# schematic_main.net
KiCad netlist of a schematic drawn in Altium Designer
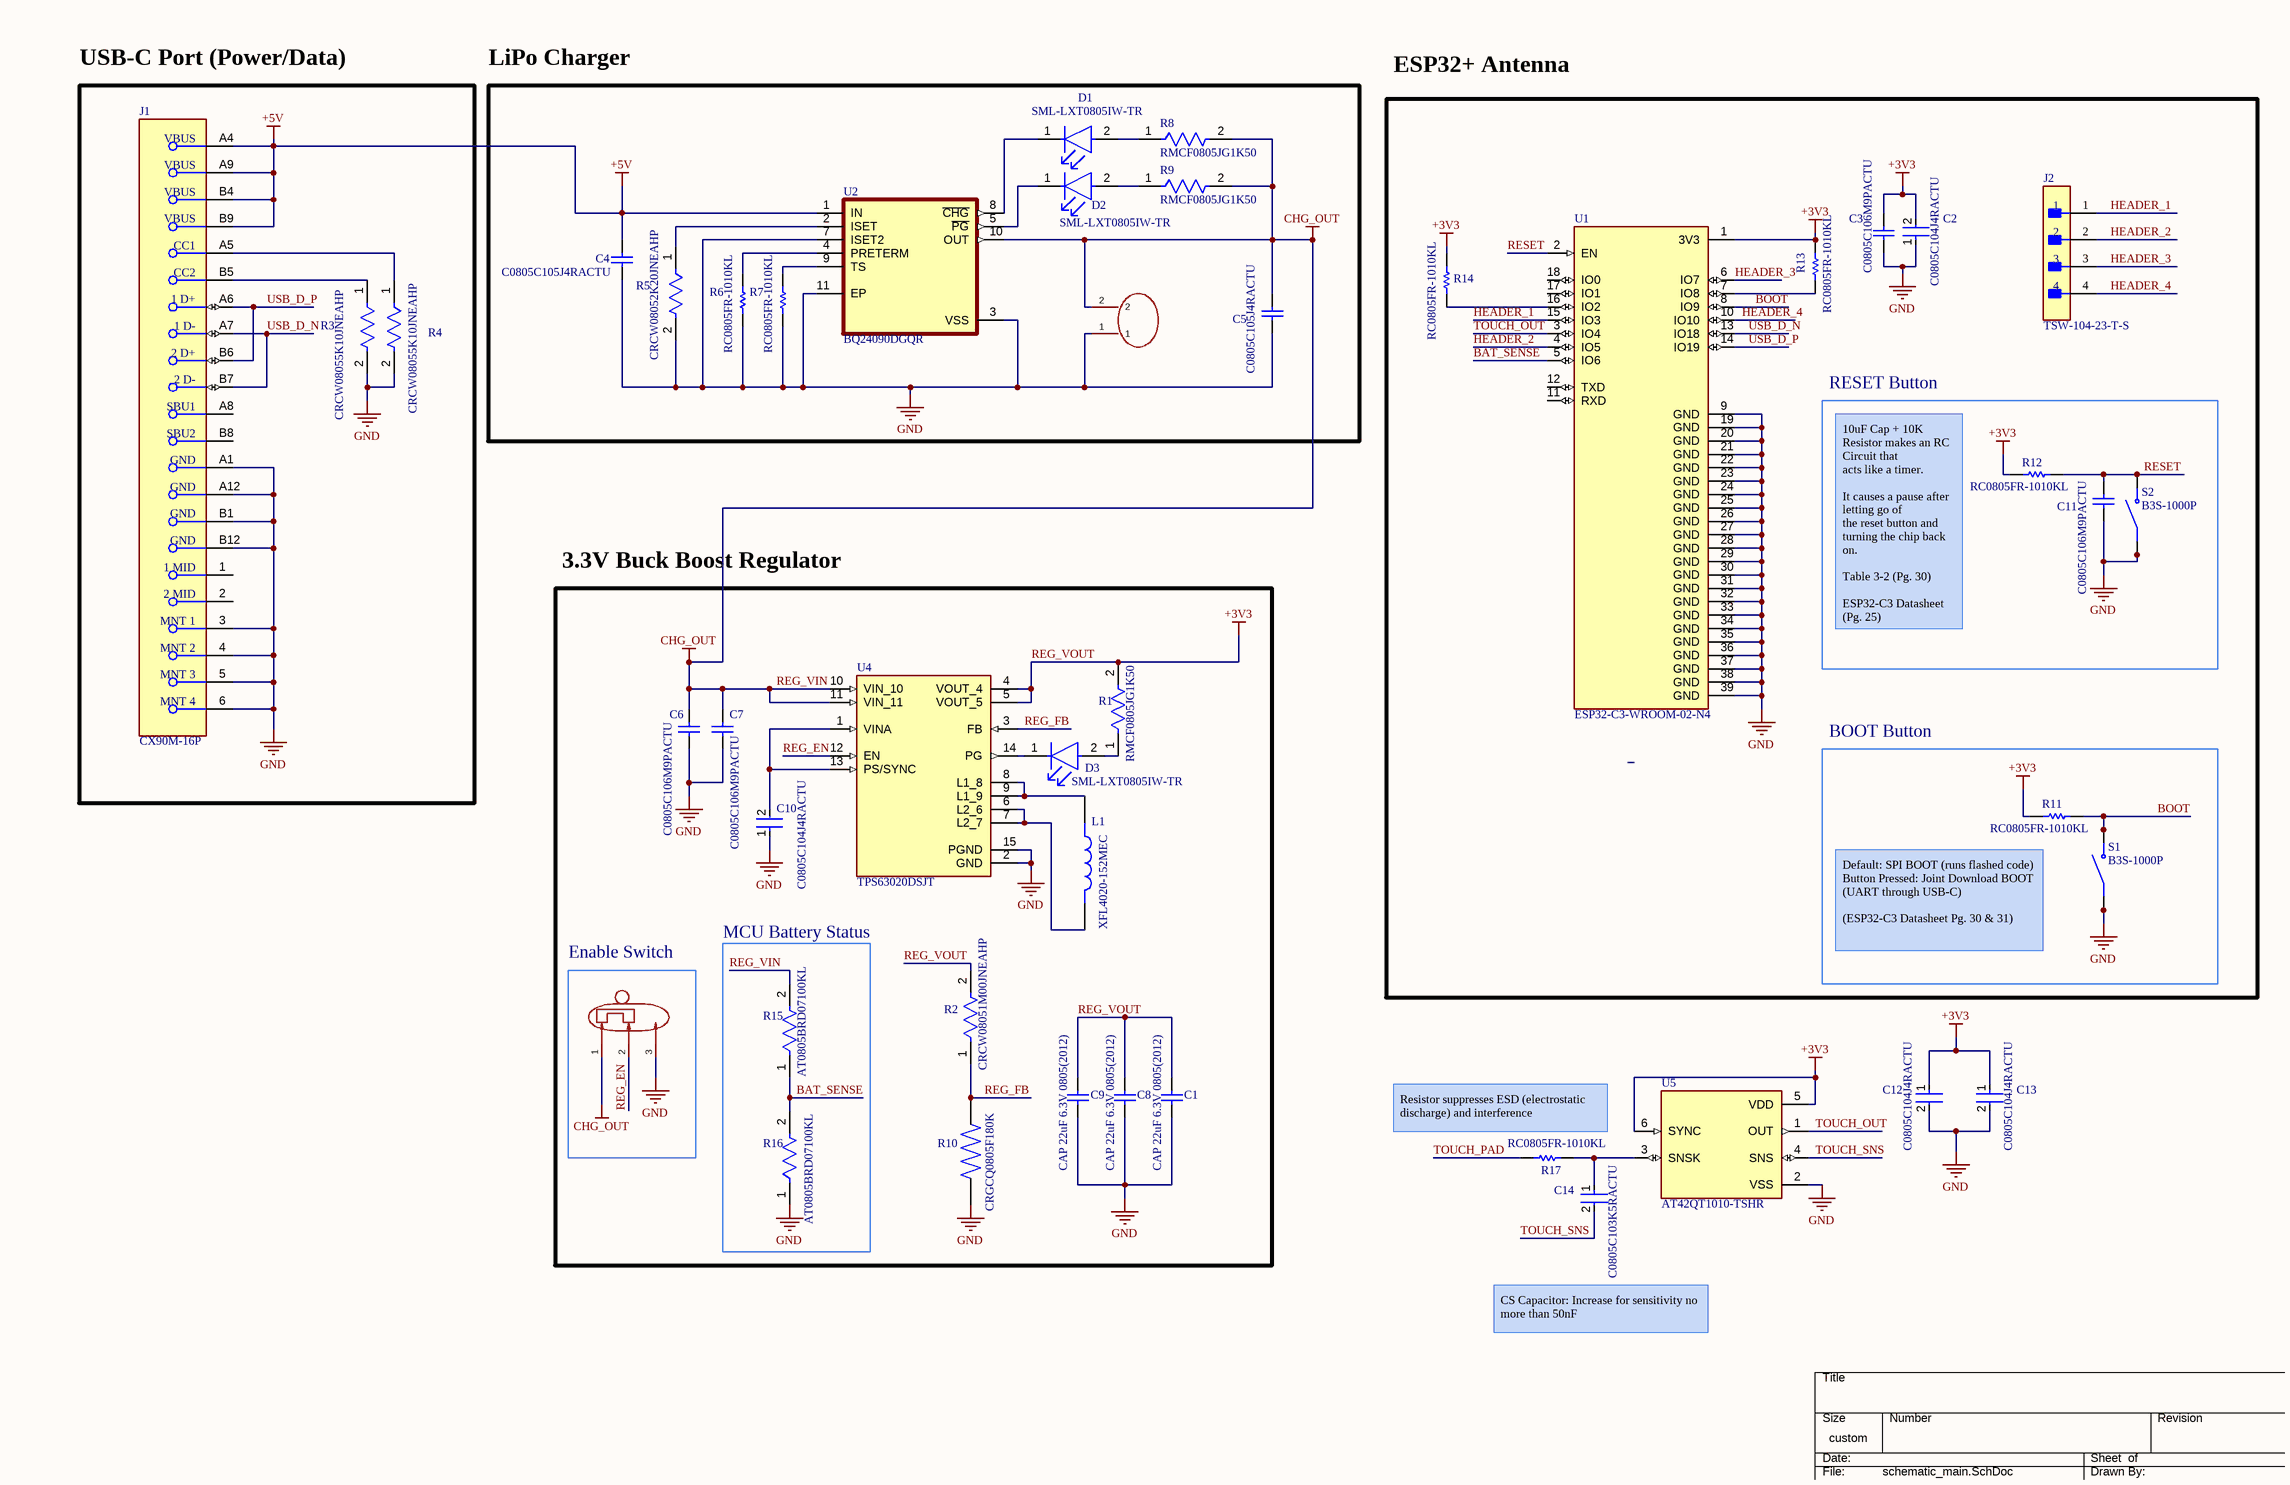
[diagram p0: schematic_main.SchDoc]

(export (version "E")
  (design (tool "Eeschema 10.0.6"))
  (components
    (comp (ref "C1")
      (value "CAP 22uF 6.3V 0805(2012)")
      (footprint "CAPC0805(2012)145_L")
      (description "CAP 22uF 6.3V ±10% 0805 (2012 Metric) Thickness 1.45mm SMD")
      (fields (field (name "TOLERANCE") "Â±10%"))
      (libsource (lib "schematic_library") (part "CMP-1036-04938-1"))
    )
    (comp (ref "C2")
      (value "C0805C104J4RACTU")
      (footprint "FP-C0805C-DN-IPC_A")
      (description "CAP CER 0.1UF 16V X7R 0805")
      (fields
        (field (name "OCTOPART") "https://octopart.com/c0805c104j4ractu-kemet-12563748")
        (field (name "MANUFACTURER") "KEMET")
      )
      (libsource (lib "schematic_library") (part "CMP-2007-01112-2"))
    )
    (comp (ref "C3")
      (value "C0805C106M9PACTU")
      (footprint "CAPC2013X145X50LL20T25")
      (description "CAP CER 10UF 6.3V X5R 0805")
      (fields (field (name "MANUFACTURER") "Kemet"))
      (libsource (lib "schematic_library") (part "CMP-1036-04919-2"))
    )
    (comp (ref "C4")
      (value "C0805C105J4RACTU")
      (footprint "CAPC2013X140X50LL20T25")
      (description "1 µF ±5% 16V Ceramic Capacitor X7R 0805 (2012 Metric)")
      (fields (field (name "MANUFACTURER") "Kemet"))
      (libsource (lib "schematic_library") (part "CMP-2007-03229-1"))
    )
    (comp (ref "C5")
      (value "C0805C105J4RACTU")
      (footprint "CAPC2013X140X50LL20T25")
      (description "1 µF ±5% 16V Ceramic Capacitor X7R 0805 (2012 Metric)")
      (fields (field (name "MANUFACTURER") "Kemet"))
      (libsource (lib "schematic_library") (part "CMP-2007-03229-1"))
    )
    (comp (ref "C6")
      (value "C0805C106M9PACTU")
      (footprint "CAPC2013X145X50LL20T25")
      (description "CAP CER 10UF 6.3V X5R 0805")
      (fields (field (name "MANUFACTURER") "Kemet"))
      (libsource (lib "schematic_library") (part "CMP-1036-04919-2"))
    )
    (comp (ref "C7")
      (value "C0805C106M9PACTU")
      (footprint "CAPC2013X145X50LL20T25")
      (description "CAP CER 10UF 6.3V X5R 0805")
      (fields (field (name "MANUFACTURER") "Kemet"))
      (libsource (lib "schematic_library") (part "CMP-1036-04919-2"))
    )
    (comp (ref "C8")
      (value "CAP 22uF 6.3V 0805(2012)")
      (footprint "CAPC0805(2012)145_L")
      (description "CAP 22uF 6.3V ±10% 0805 (2012 Metric) Thickness 1.45mm SMD")
      (fields (field (name "TOLERANCE") "Â±10%"))
      (libsource (lib "schematic_library") (part "CMP-1036-04938-1"))
    )
    (comp (ref "C9")
      (value "CAP 22uF 6.3V 0805(2012)")
      (footprint "CAPC0805(2012)145_L")
      (description "CAP 22uF 6.3V ±10% 0805 (2012 Metric) Thickness 1.45mm SMD")
      (fields (field (name "TOLERANCE") "Â±10%"))
      (libsource (lib "schematic_library") (part "CMP-1036-04938-1"))
    )
    (comp (ref "C10")
      (value "C0805C104J4RACTU")
      (footprint "FP-C0805C-DN-IPC_A")
      (description "CAP CER 0.1UF 16V X7R 0805")
      (fields
        (field (name "OCTOPART") "https://octopart.com/c0805c104j4ractu-kemet-12563748")
        (field (name "MANUFACTURER") "KEMET")
      )
      (libsource (lib "schematic_library") (part "CMP-2007-01112-2"))
    )
    (comp (ref "C11")
      (value "C0805C106M9PACTU")
      (footprint "CAPC2013X145X50LL20T25")
      (description "CAP CER 10UF 6.3V X5R 0805")
      (fields (field (name "MANUFACTURER") "Kemet"))
      (libsource (lib "schematic_library") (part "CMP-1036-04919-2"))
    )
    (comp (ref "C12")
      (value "C0805C104J4RACTU")
      (footprint "FP-C0805C-DN-IPC_A")
      (description "CAP CER 0.1UF 16V X7R 0805")
      (fields
        (field (name "OCTOPART") "https://octopart.com/c0805c104j4ractu-kemet-12563748")
        (field (name "MANUFACTURER") "KEMET")
      )
      (libsource (lib "schematic_library") (part "CMP-2007-01112-2"))
    )
    (comp (ref "C13")
      (value "C0805C104J4RACTU")
      (footprint "FP-C0805C-DN-IPC_A")
      (description "CAP CER 0.1UF 16V X7R 0805")
      (fields
        (field (name "OCTOPART") "https://octopart.com/c0805c104j4ractu-kemet-12563748")
        (field (name "MANUFACTURER") "KEMET")
      )
      (libsource (lib "schematic_library") (part "CMP-2007-01112-2"))
    )
    (comp (ref "C14")
      (value "C0805C103K5RACTU")
      (footprint "FP-C0805C-DN-IPC_A")
      (description "CAP CER 10000PF 50V X7R 0805")
      (fields
        (field (name "TOLERANCE") "0.1")
        (field (name "OCTOPART") "https://octopart.com/c0805c103k5ractu-kemet-90536")
      )
      (libsource (lib "schematic_library") (part "CMP-2007-01079-2"))
    )
    (comp (ref "CN1")
      (value "b2b-ph-k-s(lf)(sn)")
      (footprint "CONN-TH_B2B-PH-K-S")
      (fields (field (name "MANUFACTURER") "JST") (field (name "MANUFACTURERPART") "B2B-PH-K-S(LF)(SN)"))
      (libsource (lib "schematic_library") (part "b2b-ph-k-s(lf)(sn)"))
    )
    (comp (ref "D1")
      (value "SML-LXT0805IW-TR")
      (footprint "FP-SML-LXT0805IW-TR-MFG")
      (description "LED RED DIFFUSED SMD")
      (libsource (lib "schematic_library") (part "CMP-1724-00002-2"))
    )
    (comp (ref "D2")
      (value "SML-LXT0805IW-TR")
      (footprint "FP-SML-LXT0805IW-TR-MFG")
      (description "LED RED DIFFUSED SMD")
      (libsource (lib "schematic_library") (part "CMP-1724-00002-2"))
    )
    (comp (ref "D3")
      (value "SML-LXT0805IW-TR")
      (footprint "FP-SML-LXT0805IW-TR-MFG")
      (description "LED RED DIFFUSED SMD")
      (libsource (lib "schematic_library") (part "CMP-1724-00002-2"))
    )
    (comp (ref "J1")
      (value "CX90M-16P")
      (footprint "FP-CX90M-16P-MFG")
      (description "CONN RCPT USB2.0 TYPEC 16POS SMD")
      (libsource (lib "schematic_library") (part "CMP-11601-000005-1"))
    )
    (comp (ref "J2")
      (value "TSW-104-23-T-S")
      (footprint "FP-TSW-104-23-T-S-MFG")
      (description "CONN HEADER VERT 4POS 2.54MM")
      (libsource (lib "schematic_library") (part "CMP-02766-001388-1"))
    )
    (comp (ref "L1")
      (value "XFL4020-152MEC")
      (footprint "IND_XFL4020-152MEC")
      (fields (field (name "MF") "Coilcraft"))
      (libsource (lib "schematic_library") (part "XFL4020-152MEC"))
    )
    (comp (ref "R1")
      (value "RMCF0805JG1K50")
      (footprint "FP-RMCF0805-IPC_A")
      (description "1.5kΩ ±5% 0.125W 0805 Thick Film Chip Resistor AEC-Q200 compliant")
      (fields (field (name "TOLERANCE") "5%"))
      (libsource (lib "schematic_library") (part "CMP-26527-004339-1"))
    )
    (comp (ref "R2")
      (value "CRCW08051M00JNEAHP")
      (footprint "FP-CRCW0805-HPe3-IPC_A")
      (description "RES Thick Film, 1MΩ, 5%, 0.5W, 200ppm/°C, 0805")
      (fields (field (name "TOLERANCE") "5%"))
      (libsource (lib "schematic_library") (part "CMP-02407-004826-1"))
    )
    (comp (ref "R3")
      (value "CRCW08055K10JNEAHP")
      (footprint "FP-CRCW0805-HPe3-IPC_A")
      (description "RES Thick Film, 5.1kΩ, 5%, 0.5W, 200ppm/°C, 0805")
      (fields (field (name "TOLERANCE") "5%"))
      (libsource (lib "schematic_library") (part "CMP-02407-002962-1"))
    )
    (comp (ref "R4")
      (value "CRCW08055K10JNEAHP")
      (footprint "FP-CRCW0805-HPe3-IPC_A")
      (description "RES Thick Film, 5.1kΩ, 5%, 0.5W, 200ppm/°C, 0805")
      (fields (field (name "TOLERANCE") "5%"))
      (libsource (lib "schematic_library") (part "CMP-02407-002962-1"))
    )
    (comp (ref "R5")
      (value "CRCW08052K20JNEAHP")
      (footprint "FP-CRCW0805-HPe3-IPC_A")
      (description "RES Thick Film, 2.2kΩ, 5%, 0.5W, 200ppm/°C, 0805")
      (fields (field (name "TOLERANCE") "5%"))
      (libsource (lib "schematic_library") (part "CMP-02407-006246-1"))
    )
    (comp (ref "R6")
      (value "RC0805FR-1010KL")
      (footprint "RESC2013X60X35LL10T20")
      (description "RES 10K OHM 1% 1/8W 0805")
      (fields (field (name "MANUFACTURER") "Yageo"))
      (libsource (lib "schematic_library") (part "CMP-2001-04512-1"))
    )
    (comp (ref "R7")
      (value "RC0805FR-1010KL")
      (footprint "RESC2013X60X35LL10T20")
      (description "RES 10K OHM 1% 1/8W 0805")
      (fields (field (name "MANUFACTURER") "Yageo"))
      (libsource (lib "schematic_library") (part "CMP-2001-04512-1"))
    )
    (comp (ref "R8")
      (value "RMCF0805JG1K50")
      (footprint "FP-RMCF0805-IPC_A")
      (description "1.5kΩ ±5% 0.125W 0805 Thick Film Chip Resistor AEC-Q200 compliant")
      (fields (field (name "TOLERANCE") "5%"))
      (libsource (lib "schematic_library") (part "CMP-26527-004339-1"))
    )
    (comp (ref "R9")
      (value "RMCF0805JG1K50")
      (footprint "FP-RMCF0805-IPC_A")
      (description "1.5kΩ ±5% 0.125W 0805 Thick Film Chip Resistor AEC-Q200 compliant")
      (fields (field (name "TOLERANCE") "5%"))
      (libsource (lib "schematic_library") (part "CMP-26527-004339-1"))
    )
    (comp (ref "R10")
      (value "CRGCQ0805F180K")
      (footprint "RESC2012X65N")
      (fields (field (name "MF") "TE Connectivity"))
      (libsource (lib "schematic_library") (part "CRGCQ0805F180K"))
    )
    (comp (ref "R11")
      (value "RC0805FR-1010KL")
      (footprint "RESC2013X60X35LL10T20")
      (description "RES 10K OHM 1% 1/8W 0805")
      (fields (field (name "MANUFACTURER") "Yageo"))
      (libsource (lib "schematic_library") (part "CMP-2001-04512-1"))
    )
    (comp (ref "R12")
      (value "RC0805FR-1010KL")
      (footprint "RESC2013X60X35LL10T20")
      (description "RES 10K OHM 1% 1/8W 0805")
      (fields (field (name "MANUFACTURER") "Yageo"))
      (libsource (lib "schematic_library") (part "CMP-2001-04512-1"))
    )
    (comp (ref "R13")
      (value "RC0805FR-1010KL")
      (footprint "RESC2013X60X35LL10T20")
      (description "RES 10K OHM 1% 1/8W 0805")
      (fields (field (name "MANUFACTURER") "Yageo"))
      (libsource (lib "schematic_library") (part "CMP-2001-04512-1"))
    )
    (comp (ref "R14")
      (value "RC0805FR-1010KL")
      (footprint "RESC2013X60X35LL10T20")
      (description "RES 10K OHM 1% 1/8W 0805")
      (fields (field (name "MANUFACTURER") "Yageo"))
      (libsource (lib "schematic_library") (part "CMP-2001-04512-1"))
    )
    (comp (ref "R15")
      (value "AT0805BRD07100KL")
      (footprint "FP-AT0805-IPC_A")
      (description "Thin Film Chip Resistors Automotive Grade 100kΩ 0.1% 25ppm/°C 0805")
      (fields (field (name "TOLERANCE") "0.1%"))
      (libsource (lib "schematic_library") (part "CMP-03412-042085-1"))
    )
    (comp (ref "R16")
      (value "AT0805BRD07100KL")
      (footprint "FP-AT0805-IPC_A")
      (description "Thin Film Chip Resistors Automotive Grade 100kΩ 0.1% 25ppm/°C 0805")
      (fields (field (name "TOLERANCE") "0.1%"))
      (libsource (lib "schematic_library") (part "CMP-03412-042085-1"))
    )
    (comp (ref "R17")
      (value "RC0805FR-1010KL")
      (footprint "RESC2013X60X35LL10T20")
      (description "RES 10K OHM 1% 1/8W 0805")
      (fields (field (name "MANUFACTURER") "Yageo"))
      (libsource (lib "schematic_library") (part "CMP-2001-04512-1"))
    )
    (comp (ref "S1")
      (value "B3S-1000P")
      (footprint "SW_B3S-1000P")
      (description "Tactile Switch SPST-NO Top Actuated Surface Mount")
      (libsource (lib "schematic_library") (part "B3S-1000P"))
    )
    (comp (ref "S2")
      (value "B3S-1000P")
      (footprint "SW_B3S-1000P")
      (description "Tactile Switch SPST-NO Top Actuated Surface Mount")
      (libsource (lib "schematic_library") (part "B3S-1000P"))
    )
    (comp (ref "U1")
      (value "ESP32-C3-WROOM-02-N4")
      (footprint "MODULE_ESP32-C3-WROOM-02-H4")
      (fields (field (name "MF") "Espressif Systems"))
      (libsource (lib "schematic_library") (part "ESP32-C3-WROOM-02-N4"))
    )
    (comp (ref "U2")
      (value "BQ24090DGQR")
      (footprint "IC_XTR111AIDGQR")
      (description "1-cell, 1-A, Li-ion linear battery charger w/ 10kÎ© NTC")
      (fields (field (name "MF") "Texas Instruments"))
      (libsource (lib "schematic_library") (part "BQ24090DGQR"))
    )
    (comp (ref "U3")
      (value "ss-12d00-g3")
      (footprint "SW-TH_3P-L8.8-W3.9-P2.50_SS12D00G3")
      (fields (field (name "MANUFACTURER") "SOFNG(硕方)") (field (name "MANUFACTURERPART") "SS-12D00-G3"))
      (libsource (lib "schematic_library") (part "ss-12d00-g3"))
    )
    (comp (ref "U4")
      (value "TPS63020DSJT")
      (footprint "IC_TPS63020DSJT")
      (description "High Efficiency Single Inductor Buck-Boost Converter with 4A Switch")
      (fields (field (name "MF") "Texas Instruments"))
      (libsource (lib "schematic_library") (part "TPS63020DSJT"))
    )
    (comp (ref "U5")
      (value "AT42QT1010-TSHR")
      (footprint "SOT95P270X145-6N")
      (description "Capacitive Touch Buttons SOT-23-6")
      (fields (field (name "MF") "Microchip"))
      (libsource (lib "schematic_library") (part "AT42QT1010-TSHR"))
    )
  )
  (nets
    (net (code "1") (name "+3V3") (class "Default")
      (node (ref "C1") (pin "1") (pinfunction "1_1") (pintype "passive"))
      (node (ref "C12") (pin "1") (pinfunction "1_1") (pintype "passive"))
      (node (ref "C13") (pin "1") (pinfunction "1_1") (pintype "passive"))
      (node (ref "C2") (pin "2") (pinfunction "2_2") (pintype "passive"))
      (node (ref "C3") (pin "1") (pinfunction "1_1") (pintype "passive"))
      (node (ref "C8") (pin "1") (pinfunction "1_1") (pintype "passive"))
      (node (ref "C9") (pin "1") (pinfunction "1_1") (pintype "passive"))
      (node (ref "R1") (pin "2") (pinfunction "2_2") (pintype "passive"))
      (node (ref "R11") (pin "1") (pinfunction "1_1") (pintype "passive"))
      (node (ref "R12") (pin "1") (pinfunction "1_1") (pintype "passive"))
      (node (ref "R13") (pin "2") (pinfunction "2_2") (pintype "passive"))
      (node (ref "R14") (pin "2") (pinfunction "2_2") (pintype "passive"))
      (node (ref "R2") (pin "2") (pinfunction "2_2") (pintype "passive"))
      (node (ref "U1") (pin "1") (pinfunction "3V3_1") (pintype "power_in"))
      (node (ref "U4") (pin "4") (pinfunction "VOUT_4_4") (pintype "power_in"))
      (node (ref "U4") (pin "5") (pinfunction "VOUT_5_5") (pintype "power_in"))
      (node (ref "U5") (pin "5") (pinfunction "VDD_5") (pintype "power_in"))
      (node (ref "U5") (pin "6") (pinfunction "SYNC_6") (pintype "input"))
    )
    (net (code "2") (name "+5V") (class "Default")
      (node (ref "C4") (pin "2") (pinfunction "2_2") (pintype "passive"))
      (node (ref "J1") (pin "A4") (pinfunction "VBUS_A4") (pintype "power_in"))
      (node (ref "J1") (pin "A9") (pinfunction "VBUS_A9") (pintype "power_in"))
      (node (ref "J1") (pin "B4") (pinfunction "VBUS_B4") (pintype "power_in"))
      (node (ref "J1") (pin "B9") (pinfunction "VBUS_B9") (pintype "power_in"))
      (node (ref "U2") (pin "1") (pinfunction "IN_1") (pintype "passive"))
    )
    (net (code "3") (name "/BAT_SENSE") (class "Default")
      (node (ref "R15") (pin "1") (pinfunction "1_1") (pintype "passive"))
      (node (ref "R16") (pin "2") (pinfunction "2_2") (pintype "passive"))
      (node (ref "U1") (pin "5") (pinfunction "IO6_5") (pintype "bidirectional"))
    )
    (net (code "4") (name "/BOOT") (class "Default")
      (node (ref "R11") (pin "2") (pinfunction "2_2") (pintype "passive"))
      (node (ref "S1") (pin "3") (pinfunction "NO_3") (pintype "passive"))
      (node (ref "S1") (pin "4") (pinfunction "NO_4") (pintype "passive"))
      (node (ref "U1") (pin "8") (pinfunction "IO9_8") (pintype "bidirectional"))
    )
    (net (code "5") (name "/HEADER_1") (class "Default")
      (node (ref "J2") (pin "1") (pinfunction "1_1") (pintype "passive"))
      (node (ref "U1") (pin "15") (pinfunction "IO3_15") (pintype "bidirectional"))
    )
    (net (code "6") (name "/HEADER_2") (class "Default")
      (node (ref "J2") (pin "2") (pinfunction "2_2") (pintype "passive"))
      (node (ref "U1") (pin "4") (pinfunction "IO5_4") (pintype "bidirectional"))
    )
    (net (code "7") (name "/HEADER_3") (class "Default")
      (node (ref "J2") (pin "3") (pinfunction "3_3") (pintype "passive"))
      (node (ref "U1") (pin "6") (pinfunction "IO7_6") (pintype "bidirectional"))
    )
    (net (code "8") (name "/HEADER_4") (class "Default")
      (node (ref "J2") (pin "4") (pinfunction "4_4") (pintype "passive"))
      (node (ref "U1") (pin "10") (pinfunction "IO10_10") (pintype "bidirectional"))
    )
    (net (code "9") (name "/REG_EN") (class "Default")
      (node (ref "U3") (pin "2") (pinfunction "2_2") (pintype "passive"))
      (node (ref "U4") (pin "12") (pinfunction "EN_12") (pintype "input"))
    )
    (net (code "10") (name "/REG_FB") (class "Default")
      (node (ref "R10") (pin "2") (pinfunction "2_2") (pintype "passive"))
      (node (ref "R2") (pin "1") (pinfunction "1_1") (pintype "passive"))
      (node (ref "U4") (pin "3") (pinfunction "FB_3") (pintype "input"))
    )
    (net (code "11") (name "/RESET") (class "Default")
      (node (ref "C11") (pin "2") (pinfunction "2_2") (pintype "passive"))
      (node (ref "R12") (pin "2") (pinfunction "2_2") (pintype "passive"))
      (node (ref "S2") (pin "3") (pinfunction "NO_3") (pintype "passive"))
      (node (ref "S2") (pin "4") (pinfunction "NO_4") (pintype "passive"))
      (node (ref "U1") (pin "2") (pinfunction "EN_2") (pintype "input"))
    )
    (net (code "12") (name "/TOUCH_OUT") (class "Default")
      (node (ref "U1") (pin "3") (pinfunction "IO4_3") (pintype "bidirectional"))
      (node (ref "U5") (pin "1") (pinfunction "OUT_1") (pintype "output"))
    )
    (net (code "13") (name "/TOUCH_PAD") (class "Default")
      (node (ref "R17") (pin "1") (pinfunction "1_1") (pintype "passive"))
    )
    (net (code "14") (name "/TOUCH_SNS") (class "Default")
      (node (ref "C14") (pin "2") (pinfunction "2_2") (pintype "passive"))
      (node (ref "U5") (pin "4") (pinfunction "SNS_4") (pintype "bidirectional"))
    )
    (net (code "15") (name "/USB_D_N") (class "Default")
      (node (ref "J1") (pin "A7") (pinfunction "1_D-_A7") (pintype "bidirectional"))
      (node (ref "J1") (pin "B7") (pinfunction "2_D-_B7") (pintype "bidirectional"))
      (node (ref "U1") (pin "13") (pinfunction "IO18_13") (pintype "bidirectional"))
    )
    (net (code "16") (name "/USB_D_P") (class "Default")
      (node (ref "J1") (pin "A6") (pinfunction "1_D+_A6") (pintype "bidirectional"))
      (node (ref "J1") (pin "B6") (pinfunction "2_D+_B6") (pintype "bidirectional"))
      (node (ref "U1") (pin "14") (pinfunction "IO19_14") (pintype "bidirectional"))
    )
    (net (code "17") (name "CHG_OUT") (class "Default")
      (node (ref "C5") (pin "2") (pinfunction "2_2") (pintype "passive"))
      (node (ref "C6") (pin "2") (pinfunction "2_2") (pintype "passive"))
      (node (ref "C7") (pin "2") (pinfunction "2_2") (pintype "passive"))
      (node (ref "CN1") (pin "2") (pinfunction "2_2") (pintype "passive"))
      (node (ref "R15") (pin "2") (pinfunction "2_2") (pintype "passive"))
      (node (ref "R8") (pin "2") (pinfunction "2_2") (pintype "passive"))
      (node (ref "R9") (pin "2") (pinfunction "2_2") (pintype "passive"))
      (node (ref "U2") (pin "10") (pinfunction "OUT_10") (pintype "output"))
      (node (ref "U3") (pin "1") (pinfunction "1_1") (pintype "passive"))
      (node (ref "U4") (pin "10") (pinfunction "VIN_10_10") (pintype "input"))
      (node (ref "U4") (pin "11") (pinfunction "VIN_11_11") (pintype "input"))
    )
    (net (code "18") (name "GND") (class "Default")
      (node (ref "C1") (pin "2") (pinfunction "2_2") (pintype "passive"))
      (node (ref "C10") (pin "1") (pinfunction "1_1") (pintype "passive"))
      (node (ref "C11") (pin "1") (pinfunction "1_1") (pintype "passive"))
      (node (ref "C12") (pin "2") (pinfunction "2_2") (pintype "passive"))
      (node (ref "C13") (pin "2") (pinfunction "2_2") (pintype "passive"))
      (node (ref "C2") (pin "1") (pinfunction "1_1") (pintype "passive"))
      (node (ref "C3") (pin "2") (pinfunction "2_2") (pintype "passive"))
      (node (ref "C4") (pin "1") (pinfunction "1_1") (pintype "passive"))
      (node (ref "C5") (pin "1") (pinfunction "1_1") (pintype "passive"))
      (node (ref "C6") (pin "1") (pinfunction "1_1") (pintype "passive"))
      (node (ref "C7") (pin "1") (pinfunction "1_1") (pintype "passive"))
      (node (ref "C8") (pin "2") (pinfunction "2_2") (pintype "passive"))
      (node (ref "C9") (pin "2") (pinfunction "2_2") (pintype "passive"))
      (node (ref "CN1") (pin "1") (pinfunction "1_1") (pintype "passive"))
      (node (ref "J1") (pin "3") (pinfunction "MNT_1_3") (pintype "passive"))
      (node (ref "J1") (pin "4") (pinfunction "MNT_2_4") (pintype "passive"))
      (node (ref "J1") (pin "5") (pinfunction "MNT_3_5") (pintype "passive"))
      (node (ref "J1") (pin "6") (pinfunction "MNT_4_6") (pintype "passive"))
      (node (ref "J1") (pin "A1") (pinfunction "GND_A1") (pintype "power_in"))
      (node (ref "J1") (pin "A12") (pinfunction "GND_A12") (pintype "power_in"))
      (node (ref "J1") (pin "B1") (pinfunction "GND_B1") (pintype "power_in"))
      (node (ref "J1") (pin "B12") (pinfunction "GND_B12") (pintype "power_in"))
      (node (ref "R10") (pin "1") (pinfunction "1_1") (pintype "passive"))
      (node (ref "R16") (pin "1") (pinfunction "1_1") (pintype "passive"))
      (node (ref "R3") (pin "2") (pinfunction "2_2") (pintype "passive"))
      (node (ref "R4") (pin "2") (pinfunction "2_2") (pintype "passive"))
      (node (ref "R5") (pin "2") (pinfunction "2_2") (pintype "passive"))
      (node (ref "R6") (pin "1") (pinfunction "1_1") (pintype "passive"))
      (node (ref "R7") (pin "1") (pinfunction "1_1") (pintype "passive"))
      (node (ref "S1") (pin "1") (pinfunction "COM_1") (pintype "passive"))
      (node (ref "S1") (pin "2") (pinfunction "COM_2") (pintype "passive"))
      (node (ref "S2") (pin "1") (pinfunction "COM_1") (pintype "passive"))
      (node (ref "S2") (pin "2") (pinfunction "COM_2") (pintype "passive"))
      (node (ref "U1") (pin "19") (pinfunction "GND_19") (pintype "power_in"))
      (node (ref "U1") (pin "20") (pinfunction "GND_20") (pintype "power_in"))
      (node (ref "U1") (pin "21") (pinfunction "GND_21") (pintype "power_in"))
      (node (ref "U1") (pin "22") (pinfunction "GND_22") (pintype "power_in"))
      (node (ref "U1") (pin "23") (pinfunction "GND_23") (pintype "power_in"))
      (node (ref "U1") (pin "24") (pinfunction "GND_24") (pintype "power_in"))
      (node (ref "U1") (pin "25") (pinfunction "GND_25") (pintype "power_in"))
      (node (ref "U1") (pin "26") (pinfunction "GND_26") (pintype "power_in"))
      (node (ref "U1") (pin "27") (pinfunction "GND_27") (pintype "power_in"))
      (node (ref "U1") (pin "28") (pinfunction "GND_28") (pintype "power_in"))
      (node (ref "U1") (pin "29") (pinfunction "GND_29") (pintype "power_in"))
      (node (ref "U1") (pin "30") (pinfunction "GND_30") (pintype "power_in"))
      (node (ref "U1") (pin "31") (pinfunction "GND_31") (pintype "power_in"))
      (node (ref "U1") (pin "32") (pinfunction "GND_32") (pintype "power_in"))
      (node (ref "U1") (pin "33") (pinfunction "GND_33") (pintype "power_in"))
      (node (ref "U1") (pin "34") (pinfunction "GND_34") (pintype "power_in"))
      (node (ref "U1") (pin "35") (pinfunction "GND_35") (pintype "power_in"))
      (node (ref "U1") (pin "36") (pinfunction "GND_36") (pintype "power_in"))
      (node (ref "U1") (pin "37") (pinfunction "GND_37") (pintype "power_in"))
      (node (ref "U1") (pin "38") (pinfunction "GND_38") (pintype "power_in"))
      (node (ref "U1") (pin "39") (pinfunction "GND_39") (pintype "power_in"))
      (node (ref "U1") (pin "9") (pinfunction "GND_9") (pintype "power_in"))
      (node (ref "U2") (pin "11") (pinfunction "EP_11") (pintype "power_in"))
      (node (ref "U2") (pin "3") (pinfunction "VSS_3") (pintype "power_in"))
      (node (ref "U2") (pin "7") (pinfunction "ISET2_7") (pintype "passive"))
      (node (ref "U3") (pin "3") (pinfunction "3_3") (pintype "passive"))
      (node (ref "U4") (pin "15") (pinfunction "PGND_15") (pintype "power_in"))
      (node (ref "U4") (pin "2") (pinfunction "GND_2") (pintype "power_in"))
      (node (ref "U5") (pin "2") (pinfunction "VSS_2") (pintype "power_in"))
    )
    (net (code "19") (name "Net-(D1-A)") (class "Default")
      (node (ref "D1") (pin "2") (pinfunction "A_2") (pintype "passive"))
      (node (ref "R8") (pin "1") (pinfunction "1_1") (pintype "passive"))
    )
    (net (code "20") (name "Net-(D1-C)") (class "Default")
      (node (ref "D1") (pin "1") (pinfunction "C_1") (pintype "passive"))
      (node (ref "U2") (pin "8") (pinfunction "~{CHG}_8") (pintype "output"))
    )
    (net (code "21") (name "Net-(D2-A)") (class "Default")
      (node (ref "D2") (pin "2") (pinfunction "A_2") (pintype "passive"))
      (node (ref "R9") (pin "1") (pinfunction "1_1") (pintype "passive"))
    )
    (net (code "22") (name "Net-(D2-C)") (class "Default")
      (node (ref "D2") (pin "1") (pinfunction "C_1") (pintype "passive"))
      (node (ref "U2") (pin "5") (pinfunction "~{PG}_5") (pintype "output"))
    )
    (net (code "23") (name "Net-(D3-A)") (class "Default")
      (node (ref "D3") (pin "2") (pinfunction "A_2") (pintype "passive"))
      (node (ref "R1") (pin "1") (pinfunction "1_1") (pintype "passive"))
    )
    (net (code "24") (name "Net-(D3-C)") (class "Default")
      (node (ref "D3") (pin "1") (pinfunction "C_1") (pintype "passive"))
      (node (ref "U4") (pin "14") (pinfunction "PG_14") (pintype "output"))
    )
    (net (code "25") (name "Net-(J1-CC1)") (class "Default")
      (node (ref "J1") (pin "A5") (pinfunction "CC1_A5") (pintype "passive"))
      (node (ref "R4") (pin "1") (pinfunction "1_1") (pintype "passive"))
    )
    (net (code "26") (name "Net-(J1-CC2)") (class "Default")
      (node (ref "J1") (pin "B5") (pinfunction "CC2_B5") (pintype "passive"))
      (node (ref "R3") (pin "1") (pinfunction "1_1") (pintype "passive"))
    )
    (net (code "27") (name "Net-(U1-IO2)") (class "Default")
      (node (ref "R14") (pin "1") (pinfunction "1_1") (pintype "passive"))
      (node (ref "U1") (pin "16") (pinfunction "IO2_16") (pintype "bidirectional"))
    )
    (net (code "28") (name "Net-(U1-IO8)") (class "Default")
      (node (ref "R13") (pin "1") (pinfunction "1_1") (pintype "passive"))
      (node (ref "U1") (pin "7") (pinfunction "IO8_7") (pintype "bidirectional"))
    )
    (net (code "29") (name "Net-(U2-ISET)") (class "Default")
      (node (ref "R5") (pin "1") (pinfunction "1_1") (pintype "passive"))
      (node (ref "U2") (pin "2") (pinfunction "ISET_2") (pintype "passive"))
    )
    (net (code "30") (name "Net-(U2-PRETERM)") (class "Default")
      (node (ref "R6") (pin "2") (pinfunction "2_2") (pintype "passive"))
      (node (ref "U2") (pin "4") (pinfunction "PRETERM_4") (pintype "passive"))
    )
    (net (code "31") (name "Net-(U2-TS)") (class "Default")
      (node (ref "R7") (pin "2") (pinfunction "2_2") (pintype "passive"))
      (node (ref "U2") (pin "9") (pinfunction "TS_9") (pintype "passive"))
    )
    (net (code "32") (name "Net-(U4-L1_8)") (class "Default")
      (node (ref "L1") (pin "1") (pinfunction "1_1") (pintype "passive"))
      (node (ref "U4") (pin "8") (pinfunction "L1_8_8") (pintype "passive"))
      (node (ref "U4") (pin "9") (pinfunction "L1_9_9") (pintype "passive"))
    )
    (net (code "33") (name "Net-(U4-L2_6)") (class "Default")
      (node (ref "L1") (pin "2") (pinfunction "2_2") (pintype "passive"))
      (node (ref "U4") (pin "6") (pinfunction "L2_6_6") (pintype "passive"))
      (node (ref "U4") (pin "7") (pinfunction "L2_7_7") (pintype "passive"))
    )
    (net (code "34") (name "Net-(U4-PS{slash}SYNC)") (class "Default")
      (node (ref "C10") (pin "2") (pinfunction "2_2") (pintype "passive"))
      (node (ref "U4") (pin "1") (pinfunction "VINA_1") (pintype "input"))
      (node (ref "U4") (pin "13") (pinfunction "PS/SYNC_13") (pintype "input"))
    )
    (net (code "35") (name "Net-(U5-SNSK)") (class "Default")
      (node (ref "C14") (pin "1") (pinfunction "1_1") (pintype "passive"))
      (node (ref "R17") (pin "2") (pinfunction "2_2") (pintype "passive"))
      (node (ref "U5") (pin "3") (pinfunction "SNSK_3") (pintype "bidirectional"))
    )
    (net (code "36") (name "unconnected-(J1-1_MID-Pad1)") (class "Default")
      (node (ref "J1") (pin "1") (pinfunction "1_MID_1") (pintype "passive"))
    )
    (net (code "37") (name "unconnected-(J1-2_MID-Pad2)") (class "Default")
      (node (ref "J1") (pin "2") (pinfunction "2_MID_2") (pintype "passive"))
    )
    (net (code "38") (name "unconnected-(J1-SBU1-PadA8)") (class "Default")
      (node (ref "J1") (pin "A8") (pinfunction "SBU1_A8") (pintype "passive"))
    )
    (net (code "39") (name "unconnected-(J1-SBU2-PadB8)") (class "Default")
      (node (ref "J1") (pin "B8") (pinfunction "SBU2_B8") (pintype "passive"))
    )
    (net (code "40") (name "unconnected-(U1-IO0-Pad18)") (class "Default")
      (node (ref "U1") (pin "18") (pinfunction "IO0_18") (pintype "bidirectional"))
    )
    (net (code "41") (name "unconnected-(U1-IO1-Pad17)") (class "Default")
      (node (ref "U1") (pin "17") (pinfunction "IO1_17") (pintype "bidirectional"))
    )
    (net (code "42") (name "unconnected-(U1-RXD-Pad11)") (class "Default")
      (node (ref "U1") (pin "11") (pinfunction "RXD_11") (pintype "bidirectional"))
    )
    (net (code "43") (name "unconnected-(U1-TXD-Pad12)") (class "Default")
      (node (ref "U1") (pin "12") (pinfunction "TXD_12") (pintype "bidirectional"))
    )
  )
)
